# SAMC21N_Xplained_Pro_Arduino_Connectors.net
KiCad netlist of a schematic drawn in Altium Designer
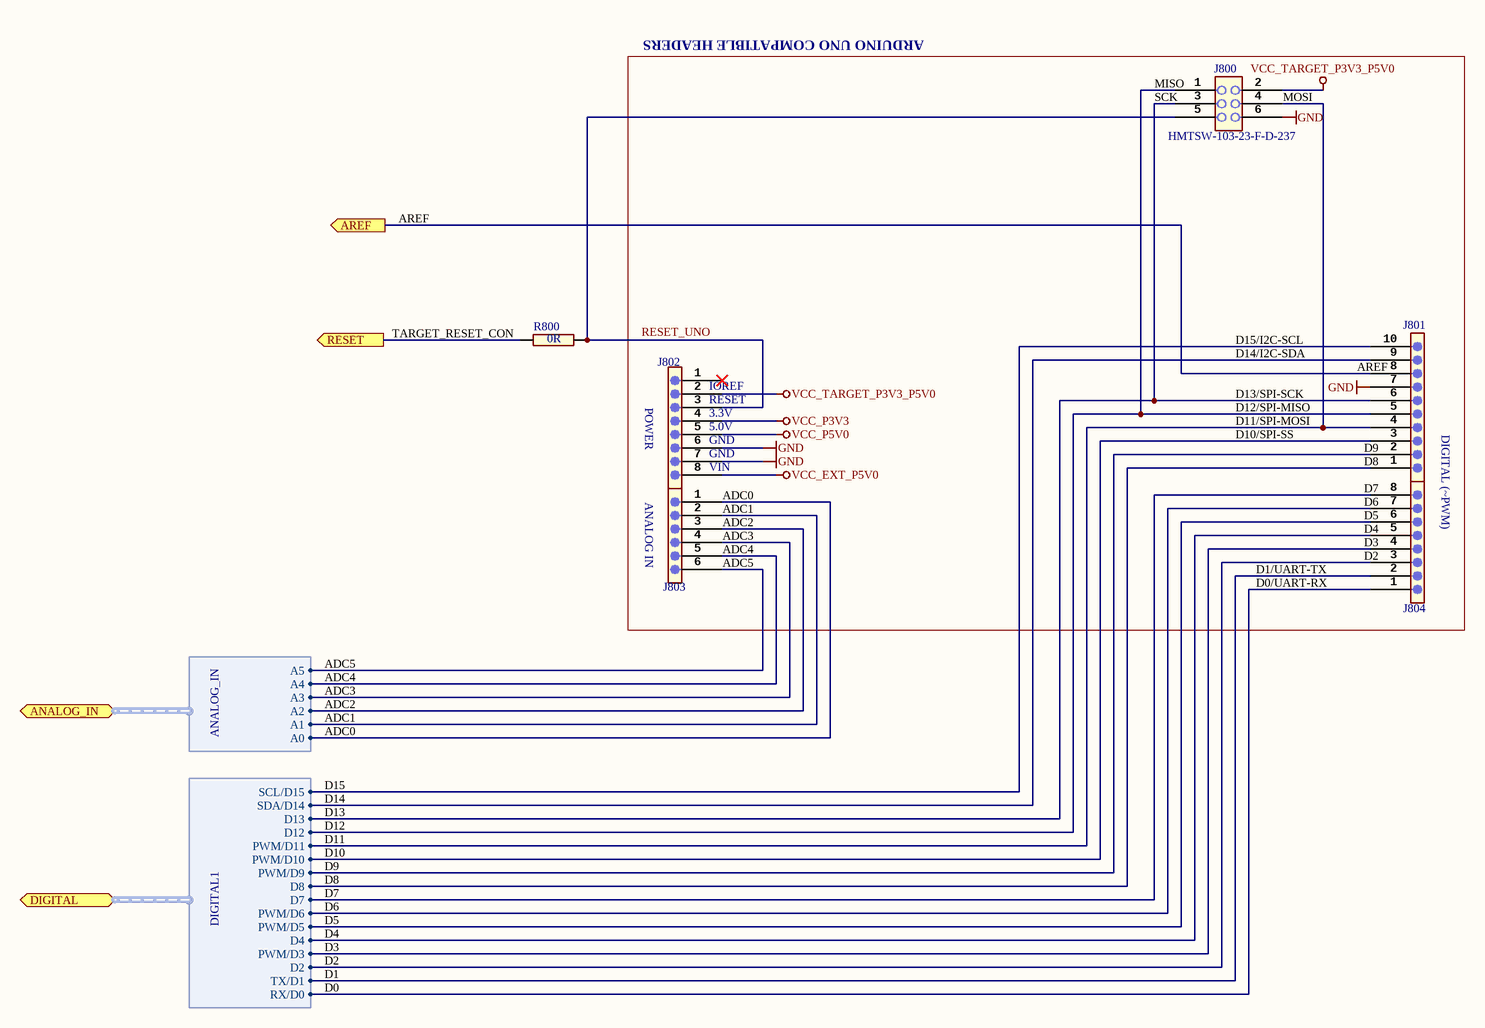
[diagram p0: SAMC21N_Xplained_Pro_Arduino_Connectors.SchDoc]

(export (version "E")
  (design (tool "Eeschema 10.0.6"))
  (components
    (comp (ref "J800")
      (value "HMTSW-103-23-F-D-237")
      (footprint "AP8-00182")
      (description "2x3 pin header, 2.54mm pitch, Pin-in-Paste THM")
      (fields
        (field (name "MANUFACTURER") "SAMTEC")
        (field (name "Comment") "HEADER 2x3")
        (field (name "VERIFIED BY") "Lars Helge Mo")
      )
      (libsource (lib "AltiumDbLib") (part "HEADER 2x3"))
    )
    (comp (ref "J801")
      (value "HEADER 1x10 FEMALE")
      (footprint "AP8-00822")
      (description "1x10 receptacle pin header, low insertion force, 2.54mm pitch THM, Pin in Paste")
      (fields (field (name "MANUFACTURER") "SAMTEC") (field (name "MPN") "SSQ-110-21-F-S"))
      (libsource (lib "AltiumDbLib") (part "HEADER 1x10 FEMALE"))
    )
    (comp (ref "J802")
      (value "HEADER 1x8 FEMALE")
      (footprint "AP8-00823")
      (description "1x8 receptacle pin header, low insertion force, 2.54mm pitch THM, Pin in Paste")
      (fields (field (name "MANUFACTURER") "SAMTEC") (field (name "MPN") "SSQ-108-21-F-S"))
      (libsource (lib "") (part "HEADER 1x8 FEMALE_1"))
    )
    (comp (ref "J803")
      (value "HEADER 1x6 FEMALE")
      (footprint "AP8-00824")
      (description "1x6 receptacle pin header, low insertion force, 2.54mm pitch THM")
      (fields
        (field (name "MANUFACTURER") "SAMTEC")
        (field (name "MPN") "SSQ-106-21-F-S")
        (field (name "VERIFIED BY") "Ketil Skjerve")
      )
      (libsource (lib "AltiumDbLib") (part "HEADER 1x6 FEMALE"))
    )
    (comp (ref "J804")
      (value "HEADER 1x8 FEMALE")
      (footprint "AP8-00823")
      (description "1x8 receptacle pin header, low insertion force, 2.54mm pitch THM, Pin in Paste")
      (fields (field (name "MANUFACTURER") "SAMTEC") (field (name "MPN") "SSQ-108-21-F-S"))
      (libsource (lib "AltiumDbLib") (part "HEADER 1x8 FEMALE"))
    )
    (comp (ref "R800")
      (value "0R")
      (footprint "AP2-00000")
      (description "RES 0.0 OHM 1/16W 0402 SMD")
      (fields
        (field (name "TOLERANCE") "1 %")
        (field (name "MANUFACTURER") "(n/a)")
        (field (name "VERIFIED BY") "Lars Helge Mo")
      )
      (libsource (lib "AltiumDbLib") (part "R2"))
    )
  )
  (nets
    (net (code "3") (name "/A0") (class "Default")
      (node (ref "J803") (pin "1") (pinfunction "1_1") (pintype "passive"))
    )
    (net (code "4") (name "/A1") (class "Default")
      (node (ref "J803") (pin "2") (pinfunction "2_2") (pintype "passive"))
    )
    (net (code "5") (name "/A2") (class "Default")
      (node (ref "J803") (pin "3") (pinfunction "3_3") (pintype "passive"))
    )
    (net (code "6") (name "/A3") (class "Default")
      (node (ref "J803") (pin "4") (pinfunction "4_4") (pintype "passive"))
    )
    (net (code "7") (name "/A4") (class "Default")
      (node (ref "J803") (pin "5") (pinfunction "5_5") (pintype "passive"))
    )
    (net (code "8") (name "/A5") (class "Default")
      (node (ref "J803") (pin "6") (pinfunction "6_6") (pintype "passive"))
    )
    (net (code "9") (name "/AREF") (class "Default")
      (node (ref "J801") (pin "8") (pinfunction "8_8") (pintype "passive"))
    )
    (net (code "10") (name "/D2") (class "Default")
      (node (ref "J804") (pin "3") (pinfunction "3_3") (pintype "passive"))
    )
    (net (code "11") (name "/D4") (class "Default")
      (node (ref "J804") (pin "5") (pinfunction "5_5") (pintype "passive"))
    )
    (net (code "12") (name "/D7") (class "Default")
      (node (ref "J804") (pin "8") (pinfunction "8_8") (pintype "passive"))
    )
    (net (code "13") (name "/D8") (class "Default")
      (node (ref "J801") (pin "1") (pinfunction "1_1") (pintype "passive"))
    )
    (net (code "14") (name "/D12") (class "Default")
      (node (ref "J800") (pin "1") (pinfunction "1_1") (pintype "passive"))
      (node (ref "J801") (pin "5") (pinfunction "5_5") (pintype "passive"))
    )
    (net (code "15") (name "/D13") (class "Default")
      (node (ref "J800") (pin "3") (pinfunction "3_3") (pintype "passive"))
      (node (ref "J801") (pin "6") (pinfunction "6_6") (pintype "passive"))
    )
    (net (code "16") (name "/PWM{slash}D3") (class "Default")
      (node (ref "J804") (pin "4") (pinfunction "4_4") (pintype "passive"))
    )
    (net (code "17") (name "/PWM{slash}D5") (class "Default")
      (node (ref "J804") (pin "6") (pinfunction "6_6") (pintype "passive"))
    )
    (net (code "18") (name "/PWM{slash}D6") (class "Default")
      (node (ref "J804") (pin "7") (pinfunction "7_7") (pintype "passive"))
    )
    (net (code "19") (name "/PWM{slash}D9") (class "Default")
      (node (ref "J801") (pin "2") (pinfunction "2_2") (pintype "passive"))
    )
    (net (code "20") (name "/PWM{slash}D10") (class "Default")
      (node (ref "J801") (pin "3") (pinfunction "3_3") (pintype "passive"))
    )
    (net (code "21") (name "/PWM{slash}D11") (class "Default")
      (node (ref "J800") (pin "4") (pinfunction "4_4") (pintype "passive"))
      (node (ref "J801") (pin "4") (pinfunction "4_4") (pintype "passive"))
    )
    (net (code "22") (name "/RESET") (class "Default")
      (node (ref "R800") (pin "1") (pinfunction "1_1") (pintype "passive"))
    )
    (net (code "23") (name "/RESET_UNO") (class "Default")
      (node (ref "J800") (pin "5") (pinfunction "5_5") (pintype "passive"))
      (node (ref "J802") (pin "3") (pinfunction "3_3") (pintype "passive"))
      (node (ref "R800") (pin "2") (pinfunction "2_2") (pintype "passive"))
    )
    (net (code "24") (name "/RX{slash}D0") (class "Default")
      (node (ref "J804") (pin "1") (pinfunction "1_1") (pintype "passive"))
    )
    (net (code "25") (name "/SCL{slash}D15") (class "Default")
      (node (ref "J801") (pin "10") (pinfunction "10_10") (pintype "passive"))
    )
    (net (code "26") (name "/SDA{slash}D14") (class "Default")
      (node (ref "J801") (pin "9") (pinfunction "9_9") (pintype "passive"))
    )
    (net (code "27") (name "/TX{slash}D1") (class "Default")
      (node (ref "J804") (pin "2") (pinfunction "2_2") (pintype "passive"))
    )
    (net (code "30") (name "GND") (class "Default")
      (node (ref "J800") (pin "6") (pinfunction "6_6") (pintype "passive"))
      (node (ref "J801") (pin "7") (pinfunction "7_7") (pintype "passive"))
      (node (ref "J802") (pin "6") (pinfunction "6_6") (pintype "passive"))
      (node (ref "J802") (pin "7") (pinfunction "7_7") (pintype "passive"))
    )
    (net (code "31") (name "VCC_EXT_P5V0") (class "Default")
      (node (ref "J802") (pin "8") (pinfunction "8_8") (pintype "passive"))
    )
    (net (code "32") (name "VCC_P3V3") (class "Default")
      (node (ref "J802") (pin "4") (pinfunction "4_4") (pintype "passive"))
    )
    (net (code "33") (name "VCC_P5V0") (class "Default")
      (node (ref "J802") (pin "5") (pinfunction "5_5") (pintype "passive"))
    )
    (net (code "34") (name "VCC_TARGET_P3V3_P5V0") (class "Default")
      (node (ref "J800") (pin "2") (pinfunction "2_2") (pintype "passive"))
      (node (ref "J802") (pin "2") (pinfunction "2_2") (pintype "passive"))
    )
    (net (code "35") (name "unconnected-(J802-Pad1)") (class "Default")
      (node (ref "J802") (pin "1") (pinfunction "1_1") (pintype "passive+no_connect"))
    )
  )
)
